# edison_mezzanine_oled.net
KiCad netlist of a schematic drawn in EAGLE
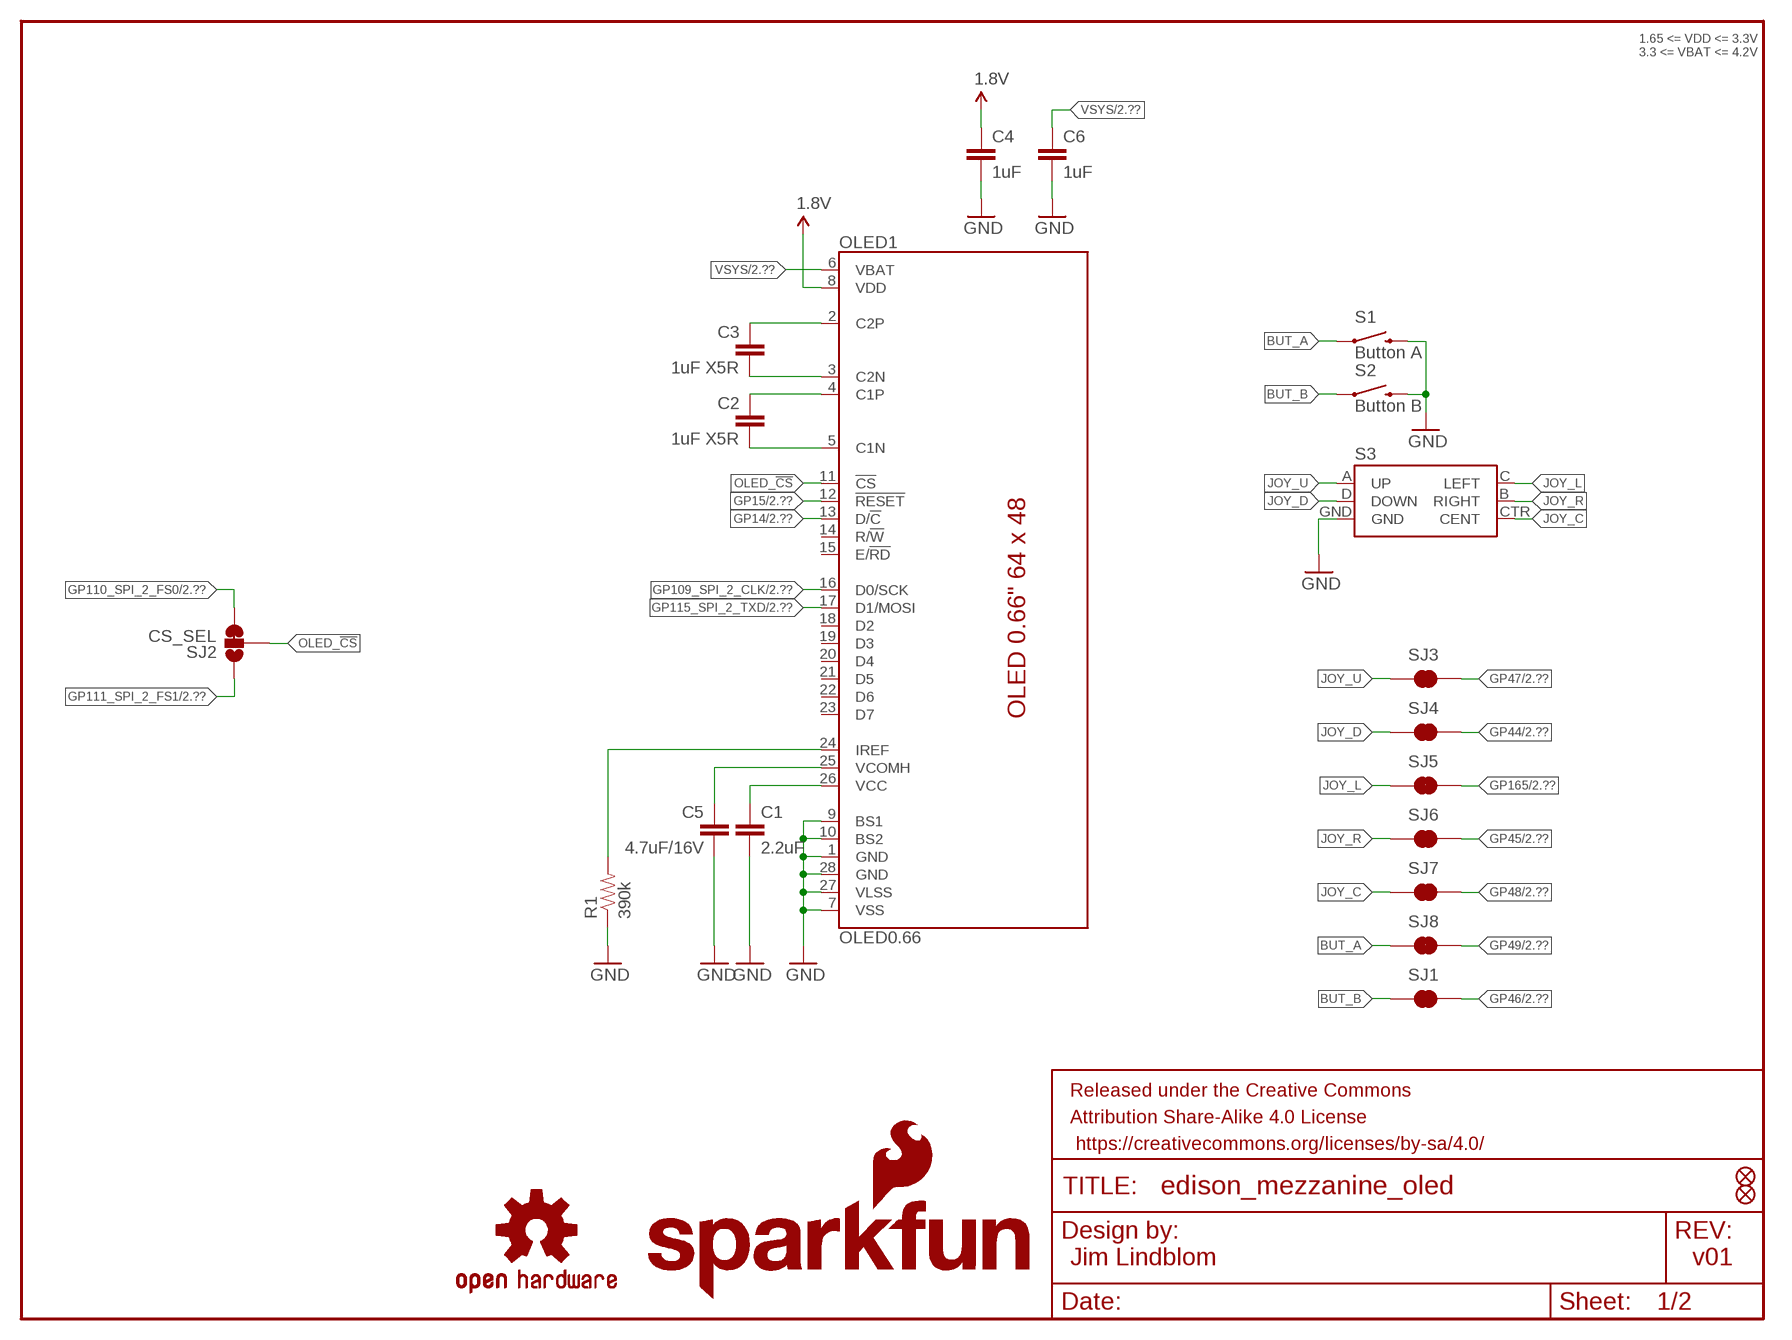
[diagram p0: schematic, sheet 1]
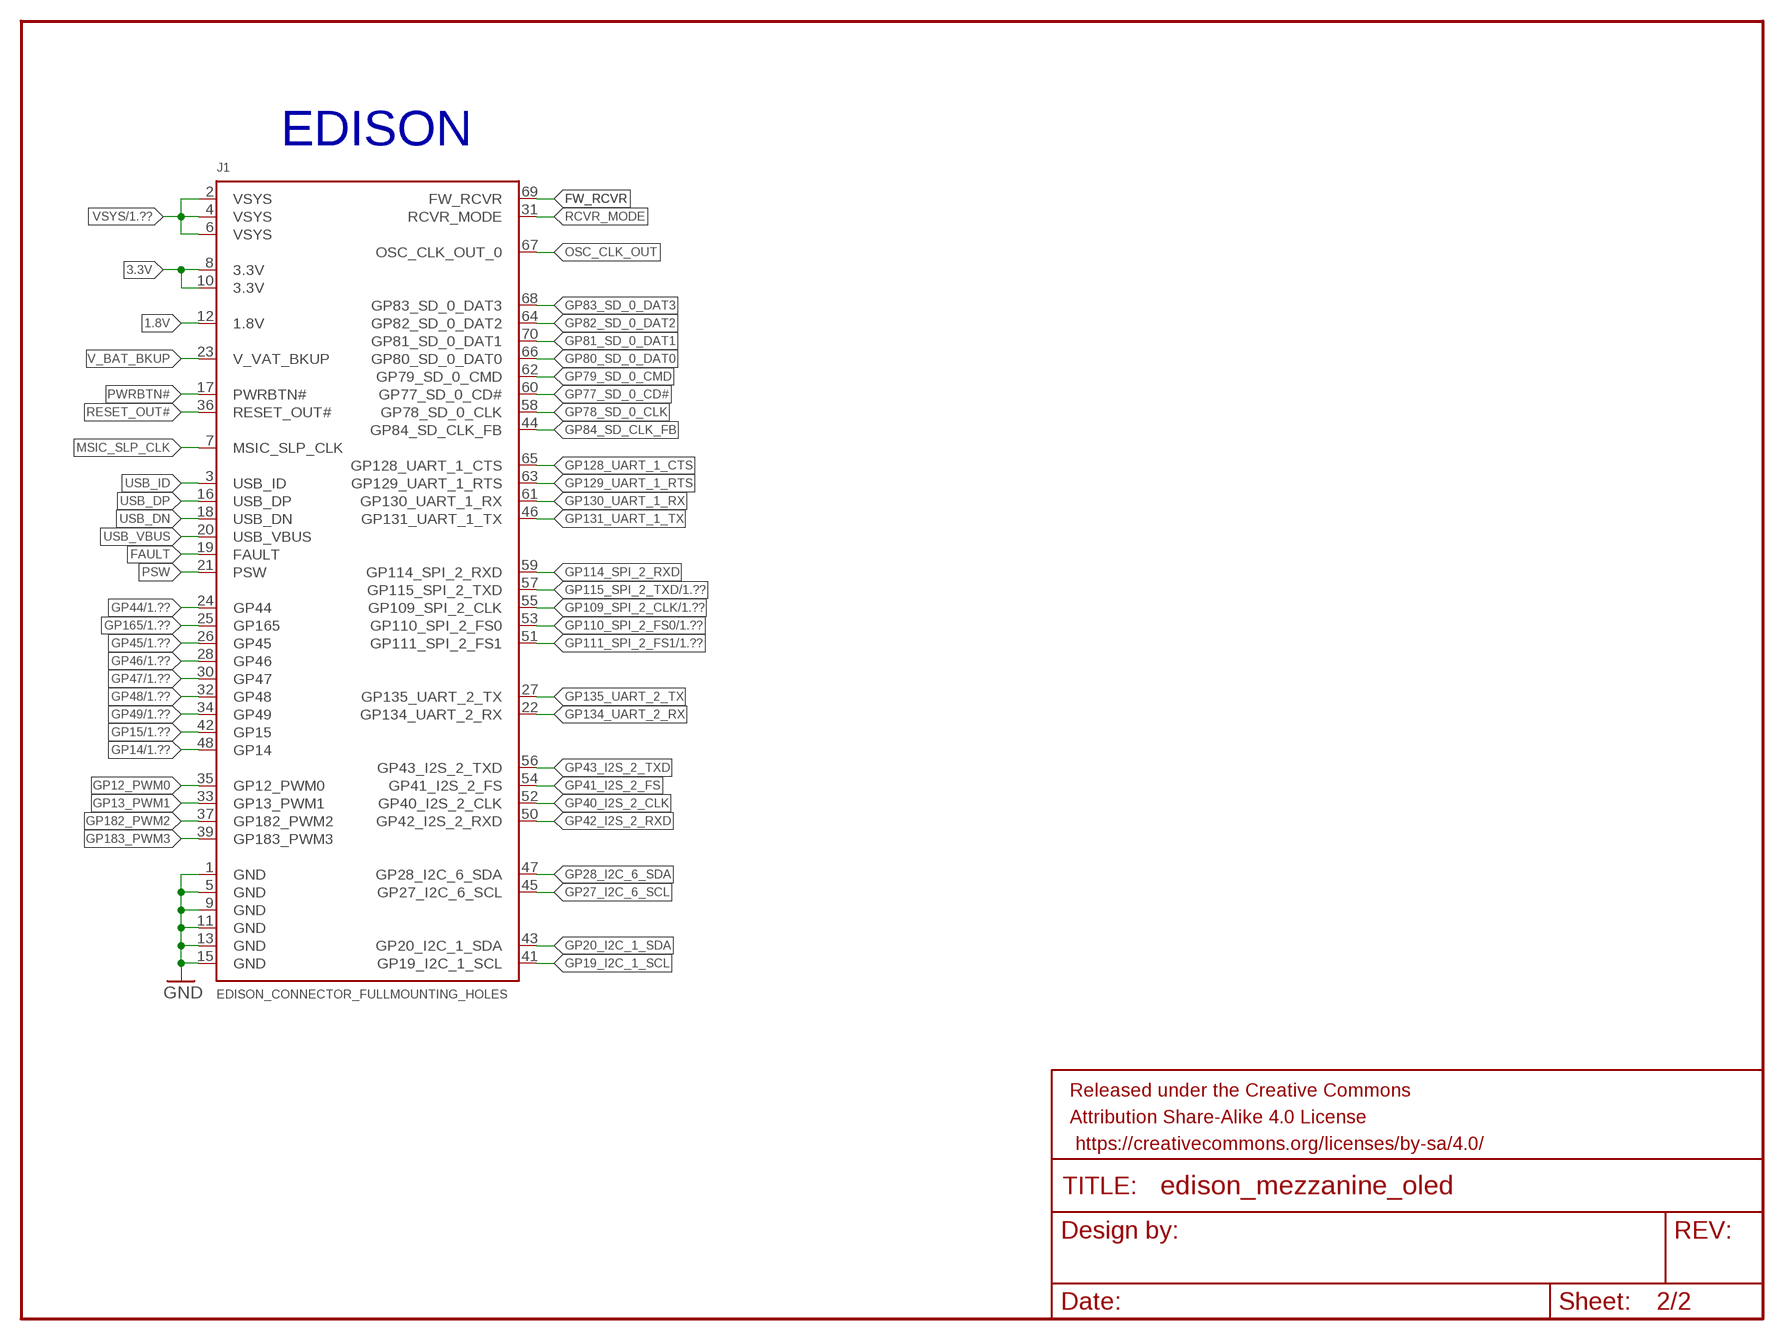
[diagram p1: schematic, sheet 2]

(export (version "E")
  (design (tool "Eeschema 10.0.6"))
  (components
    (comp (ref "C1")
      (value "2.2uF")
      (footprint "eagle-import:0805")
      (libsource (lib "eagle-import") (part "CAP0805"))
    )
    (comp (ref "C2")
      (value "1uF X5R")
      (footprint "eagle-import:0805")
      (libsource (lib "eagle-import") (part "CAP0805"))
    )
    (comp (ref "C3")
      (value "1uF X5R")
      (footprint "eagle-import:0805")
      (libsource (lib "eagle-import") (part "CAP0805"))
    )
    (comp (ref "C4")
      (value "1uF")
      (footprint "eagle-import:0603-CAP")
      (libsource (lib "eagle-import") (part "CAP0603-CAP"))
    )
    (comp (ref "C5")
      (value "4.7uF/16V")
      (footprint "eagle-import:1206")
      (libsource (lib "eagle-import") (part "CAP1206"))
    )
    (comp (ref "C6")
      (value "1uF")
      (footprint "eagle-import:0603-CAP")
      (libsource (lib "eagle-import") (part "CAP0603-CAP"))
    )
    (comp (ref "FID1")
      (value "FIDUCIAL1X2")
      (footprint "eagle-import:FIDUCIAL-1X2")
      (libsource (lib "eagle-import") (part "FIDUCIAL1X2"))
    )
    (comp (ref "FID2")
      (value "FIDUCIAL1X2")
      (footprint "eagle-import:FIDUCIAL-1X2")
      (libsource (lib "eagle-import") (part "FIDUCIAL1X2"))
    )
    (comp (ref "FRAME1")
      (value "FRAME-LETTER")
      (footprint "eagle-import:CREATIVE_COMMONS")
      (libsource (lib "eagle-import") (part "FRAME-LETTER"))
    )
    (comp (ref "LOGO1")
      (value "SFE_LOGO_NAME_FLAME.1_INCH")
      (footprint "eagle-import:SFE_LOGO_NAME_FLAME_.1")
      (libsource (lib "eagle-import") (part "SFE_LOGO_NAME_FLAME.1_INCH"))
    )
    (comp (ref "LOGO2")
      (value "OSHW-LOGOS")
      (footprint "eagle-import:OSHW-LOGO-S")
      (libsource (lib "eagle-import") (part "OSHW-LOGOS"))
    )
    (comp (ref "OLED1")
      (value "OLED0.66")
      (footprint "eagle-import:OLED-0.66-64X48")
      (libsource (lib "eagle-import") (part "OLED0.66"))
    )
    (comp (ref "R1")
      (value "390k")
      (footprint "eagle-import:0603-RES")
      (libsource (lib "eagle-import") (part "RESISTOR0603-RES"))
    )
    (comp (ref "S1")
      (value "Button A")
      (footprint "eagle-import:TACTILE-SWITCH-SMD")
      (libsource (lib "eagle-import") (part "SWITCH-MOMENTARY-2SMD"))
    )
    (comp (ref "S2")
      (value "Button B")
      (footprint "eagle-import:TACTILE-SWITCH-SMD")
      (libsource (lib "eagle-import") (part "SWITCH-MOMENTARY-2SMD"))
    )
    (comp (ref "S3")
      (value "JOYSTICK_MINI")
      (footprint "eagle-import:JOYSTICK_MINI")
      (libsource (lib "eagle-import") (part "JOYSTICK_MINI"))
    )
    (comp (ref "SJ1")
      (value "JUMPER-PAD-2-NC_BY_TRACE")
      (footprint "eagle-import:PAD-JUMPER-2-NC_BY_TRACE_YES_SILK")
      (libsource (lib "eagle-import") (part "JUMPER-PAD-2-NC_BY_TRACE"))
    )
    (comp (ref "SJ2")
      (value "CS_SEL")
      (footprint "eagle-import:PAD-JUMPER-3-2OF3_NC_BY_TRACE_YES_SILK_FULL_BOX")
      (libsource (lib "eagle-import") (part "JUMPER-PAD-3-2OF3_NC_BY_TRACE"))
    )
    (comp (ref "SJ3")
      (value "JUMPER-PAD-2-NC_BY_TRACE")
      (footprint "eagle-import:PAD-JUMPER-2-NC_BY_TRACE_YES_SILK")
      (libsource (lib "eagle-import") (part "JUMPER-PAD-2-NC_BY_TRACE"))
    )
    (comp (ref "SJ4")
      (value "JUMPER-PAD-2-NC_BY_TRACE")
      (footprint "eagle-import:PAD-JUMPER-2-NC_BY_TRACE_YES_SILK")
      (libsource (lib "eagle-import") (part "JUMPER-PAD-2-NC_BY_TRACE"))
    )
    (comp (ref "SJ5")
      (value "JUMPER-PAD-2-NC_BY_TRACE")
      (footprint "eagle-import:PAD-JUMPER-2-NC_BY_TRACE_YES_SILK")
      (libsource (lib "eagle-import") (part "JUMPER-PAD-2-NC_BY_TRACE"))
    )
    (comp (ref "SJ6")
      (value "JUMPER-PAD-2-NC_BY_TRACE")
      (footprint "eagle-import:PAD-JUMPER-2-NC_BY_TRACE_YES_SILK")
      (libsource (lib "eagle-import") (part "JUMPER-PAD-2-NC_BY_TRACE"))
    )
    (comp (ref "SJ7")
      (value "JUMPER-PAD-2-NC_BY_TRACE")
      (footprint "eagle-import:PAD-JUMPER-2-NC_BY_TRACE_YES_SILK")
      (libsource (lib "eagle-import") (part "JUMPER-PAD-2-NC_BY_TRACE"))
    )
    (comp (ref "SJ8")
      (value "JUMPER-PAD-2-NC_BY_TRACE")
      (footprint "eagle-import:PAD-JUMPER-2-NC_BY_TRACE_YES_SILK")
      (libsource (lib "eagle-import") (part "JUMPER-PAD-2-NC_BY_TRACE"))
    )
    (comp (ref "FRAME2")
      (value "FRAME-LETTER")
      (footprint "eagle-import:CREATIVE_COMMONS")
      (libsource (lib "eagle-import") (part "FRAME-LETTER"))
    )
    (comp (ref "J1")
      (value "EDISON_CONNECTOR_FULLMOUNTING_HOLES")
      (footprint "eagle-import:EDISON_DAUGHTER")
      (libsource (lib "eagle-import") (part "EDISON_CONNECTOR_FULLMOUNTING_HOLES"))
    )
  )
  (nets
    (net (code "1") (name "1.8V") (class "Default")
      (node (ref "C4") (pin "1") (pinfunction "1_1") (pintype "passive"))
      (node (ref "J1") (pin "12") (pinfunction "1.8V_12") (pintype "bidirectional"))
      (node (ref "OLED1") (pin "8") (pinfunction "VDD_8") (pintype "bidirectional"))
    )
    (net (code "2") (name "3.3V") (class "Default")
      (node (ref "J1") (pin "10") (pinfunction "3.3V_10") (pintype "bidirectional"))
      (node (ref "J1") (pin "8") (pinfunction "3.3V_8") (pintype "bidirectional"))
    )
    (net (code "3") (name "BUT_A") (class "Default")
      (node (ref "S1") (pin "1") (pinfunction "1_1") (pintype "passive"))
      (node (ref "SJ8") (pin "1") (pinfunction "1_1") (pintype "passive"))
    )
    (net (code "4") (name "BUT_B") (class "Default")
      (node (ref "S2") (pin "1") (pinfunction "1_1") (pintype "passive"))
      (node (ref "SJ1") (pin "1") (pinfunction "1_1") (pintype "passive"))
    )
    (net (code "5") (name "FAULT") (class "Default")
      (node (ref "J1") (pin "19") (pinfunction "FAULT_19") (pintype "bidirectional"))
    )
    (net (code "6") (name "FW_RCVR") (class "Default")
      (node (ref "J1") (pin "69") (pinfunction "FW_RCVR_69") (pintype "bidirectional"))
    )
    (net (code "7") (name "GND") (class "Default")
      (node (ref "C1") (pin "2") (pinfunction "2_2") (pintype "passive"))
      (node (ref "C4") (pin "2") (pinfunction "2_2") (pintype "passive"))
      (node (ref "C5") (pin "2") (pinfunction "2_2") (pintype "passive"))
      (node (ref "C6") (pin "2") (pinfunction "2_2") (pintype "passive"))
      (node (ref "J1") (pin "1") (pinfunction "GND_1") (pintype "bidirectional"))
      (node (ref "J1") (pin "11") (pinfunction "GND_11") (pintype "bidirectional"))
      (node (ref "J1") (pin "13") (pinfunction "GND_13") (pintype "bidirectional"))
      (node (ref "J1") (pin "15") (pinfunction "GND_15") (pintype "bidirectional"))
      (node (ref "J1") (pin "5") (pinfunction "GND_5") (pintype "bidirectional"))
      (node (ref "J1") (pin "9") (pinfunction "GND_9") (pintype "bidirectional"))
      (node (ref "OLED1") (pin "1") (pinfunction "GND_1") (pintype "bidirectional"))
      (node (ref "OLED1") (pin "10") (pinfunction "BS2_10") (pintype "bidirectional"))
      (node (ref "OLED1") (pin "27") (pinfunction "VLSS_27") (pintype "bidirectional"))
      (node (ref "OLED1") (pin "28") (pinfunction "GND_28") (pintype "bidirectional"))
      (node (ref "OLED1") (pin "7") (pinfunction "VSS_7") (pintype "bidirectional"))
      (node (ref "OLED1") (pin "9") (pinfunction "BS1_9") (pintype "bidirectional"))
      (node (ref "R1") (pin "1") (pinfunction "1_1") (pintype "passive"))
      (node (ref "S1") (pin "3") (pinfunction "2_3") (pintype "passive"))
      (node (ref "S2") (pin "3") (pinfunction "2_3") (pintype "passive"))
      (node (ref "S3") (pin "GND") (pinfunction "GND_GND") (pintype "bidirectional"))
    )
    (net (code "8") (name "GP12_PWM0") (class "Default")
      (node (ref "J1") (pin "35") (pinfunction "GP12_PWM0_35") (pintype "bidirectional"))
    )
    (net (code "9") (name "GP13_PWM1") (class "Default")
      (node (ref "J1") (pin "33") (pinfunction "GP13_PWM1_33") (pintype "bidirectional"))
    )
    (net (code "10") (name "GP14") (class "Default")
      (node (ref "J1") (pin "48") (pinfunction "GP14_48") (pintype "bidirectional"))
      (node (ref "OLED1") (pin "13") (pinfunction "D/~{C}_13") (pintype "bidirectional"))
    )
    (net (code "11") (name "GP15") (class "Default")
      (node (ref "J1") (pin "42") (pinfunction "GP15_42") (pintype "bidirectional"))
      (node (ref "OLED1") (pin "12") (pinfunction "~{RESET}_12") (pintype "bidirectional"))
    )
    (net (code "12") (name "GP19_I2C_1_SCL") (class "Default")
      (node (ref "J1") (pin "41") (pinfunction "GP19_I2C_1_SCL_41") (pintype "bidirectional"))
    )
    (net (code "13") (name "GP20_I2C_1_SDA") (class "Default")
      (node (ref "J1") (pin "43") (pinfunction "GP20_I2C_1_SDA_43") (pintype "bidirectional"))
    )
    (net (code "14") (name "GP27_I2C_6_SCL") (class "Default")
      (node (ref "J1") (pin "45") (pinfunction "GP27_I2C_6_SCL_45") (pintype "bidirectional"))
    )
    (net (code "15") (name "GP28_I2C_6_SDA") (class "Default")
      (node (ref "J1") (pin "47") (pinfunction "GP28_I2C_6_SDA_47") (pintype "bidirectional"))
    )
    (net (code "16") (name "GP40_I2S_2_CLK") (class "Default")
      (node (ref "J1") (pin "52") (pinfunction "GP40_I2S_2_CLK_52") (pintype "bidirectional"))
    )
    (net (code "17") (name "GP41_I2S_2_FS") (class "Default")
      (node (ref "J1") (pin "54") (pinfunction "GP41_I2S_2_FS_54") (pintype "bidirectional"))
    )
    (net (code "18") (name "GP42_I2S_2_RXD") (class "Default")
      (node (ref "J1") (pin "50") (pinfunction "GP42_I2S_2_RXD_50") (pintype "bidirectional"))
    )
    (net (code "19") (name "GP43_I2S_2_TXD") (class "Default")
      (node (ref "J1") (pin "56") (pinfunction "GP43_I2S_2_TXD_56") (pintype "bidirectional"))
    )
    (net (code "20") (name "GP44") (class "Default")
      (node (ref "J1") (pin "24") (pinfunction "GP44_24") (pintype "bidirectional"))
      (node (ref "SJ4") (pin "2") (pinfunction "2_2") (pintype "passive"))
    )
    (net (code "21") (name "GP45") (class "Default")
      (node (ref "J1") (pin "26") (pinfunction "GP45_26") (pintype "bidirectional"))
      (node (ref "SJ6") (pin "2") (pinfunction "2_2") (pintype "passive"))
    )
    (net (code "22") (name "GP46") (class "Default")
      (node (ref "J1") (pin "28") (pinfunction "GP46_28") (pintype "bidirectional"))
      (node (ref "SJ1") (pin "2") (pinfunction "2_2") (pintype "passive"))
    )
    (net (code "23") (name "GP47") (class "Default")
      (node (ref "J1") (pin "30") (pinfunction "GP47_30") (pintype "bidirectional"))
      (node (ref "SJ3") (pin "2") (pinfunction "2_2") (pintype "passive"))
    )
    (net (code "24") (name "GP48") (class "Default")
      (node (ref "J1") (pin "32") (pinfunction "GP48_32") (pintype "bidirectional"))
      (node (ref "SJ7") (pin "2") (pinfunction "2_2") (pintype "passive"))
    )
    (net (code "25") (name "GP49") (class "Default")
      (node (ref "J1") (pin "34") (pinfunction "GP49_34") (pintype "bidirectional"))
      (node (ref "SJ8") (pin "2") (pinfunction "2_2") (pintype "passive"))
    )
    (net (code "26") (name "GP77_SD_0_CD#") (class "Default")
      (node (ref "J1") (pin "60") (pinfunction "GP77_SD_0_CD#_60") (pintype "bidirectional"))
    )
    (net (code "27") (name "GP78_SD_0_CLK") (class "Default")
      (node (ref "J1") (pin "58") (pinfunction "GP78_SD_0_CLK_58") (pintype "bidirectional"))
    )
    (net (code "28") (name "GP79_SD_0_CMD") (class "Default")
      (node (ref "J1") (pin "62") (pinfunction "GP79_SD_0_CMD_62") (pintype "bidirectional"))
    )
    (net (code "29") (name "GP80_SD_0_DAT0") (class "Default")
      (node (ref "J1") (pin "66") (pinfunction "GP80_SD_0_DAT0_66") (pintype "bidirectional"))
    )
    (net (code "30") (name "GP81_SD_0_DAT1") (class "Default")
      (node (ref "J1") (pin "70") (pinfunction "GP81_SD_0_DAT1_70") (pintype "bidirectional"))
    )
    (net (code "31") (name "GP82_SD_0_DAT2") (class "Default")
      (node (ref "J1") (pin "64") (pinfunction "GP82_SD_0_DAT2_64") (pintype "bidirectional"))
    )
    (net (code "32") (name "GP83_SD_0_DAT3") (class "Default")
      (node (ref "J1") (pin "68") (pinfunction "GP83_SD_0_DAT3_68") (pintype "bidirectional"))
    )
    (net (code "33") (name "GP84_SD_CLK_FB") (class "Default")
      (node (ref "J1") (pin "44") (pinfunction "GP84_SD_CLK_FB_44") (pintype "bidirectional"))
    )
    (net (code "34") (name "GP109_SPI_2_CLK") (class "Default")
      (node (ref "J1") (pin "55") (pinfunction "GP109_SPI_2_CLK_55") (pintype "bidirectional"))
      (node (ref "OLED1") (pin "16") (pinfunction "D0/SCK_16") (pintype "bidirectional"))
    )
    (net (code "35") (name "GP110_SPI_2_FS0") (class "Default")
      (node (ref "J1") (pin "53") (pinfunction "GP110_SPI_2_FS0_53") (pintype "bidirectional"))
      (node (ref "SJ2") (pin "3") (pinfunction "3_3") (pintype "passive"))
    )
    (net (code "36") (name "GP111_SPI_2_FS1") (class "Default")
      (node (ref "J1") (pin "51") (pinfunction "GP111_SPI_2_FS1_51") (pintype "bidirectional"))
      (node (ref "SJ2") (pin "1") (pinfunction "1_1") (pintype "passive"))
    )
    (net (code "37") (name "GP114_SPI_2_RXD") (class "Default")
      (node (ref "J1") (pin "59") (pinfunction "GP114_SPI_2_RXD_59") (pintype "bidirectional"))
    )
    (net (code "38") (name "GP115_SPI_2_TXD") (class "Default")
      (node (ref "J1") (pin "57") (pinfunction "GP115_SPI_2_TXD_57") (pintype "bidirectional"))
      (node (ref "OLED1") (pin "17") (pinfunction "D1/MOSI_17") (pintype "bidirectional"))
    )
    (net (code "39") (name "GP128_UART_1_CTS") (class "Default")
      (node (ref "J1") (pin "65") (pinfunction "GP128_UART_1_CTS_65") (pintype "bidirectional"))
    )
    (net (code "40") (name "GP129_UART_1_RTS") (class "Default")
      (node (ref "J1") (pin "63") (pinfunction "GP129_UART_1_RTS_63") (pintype "bidirectional"))
    )
    (net (code "41") (name "GP130_UART_1_RX") (class "Default")
      (node (ref "J1") (pin "61") (pinfunction "GP130_UART_1_RX_61") (pintype "bidirectional"))
    )
    (net (code "42") (name "GP131_UART_1_TX") (class "Default")
      (node (ref "J1") (pin "46") (pinfunction "GP131_UART_1_TX_46") (pintype "bidirectional"))
    )
    (net (code "43") (name "GP134_UART_2_RX") (class "Default")
      (node (ref "J1") (pin "22") (pinfunction "GP134_UART_2_RX_22") (pintype "bidirectional"))
    )
    (net (code "44") (name "GP135_UART_2_TX") (class "Default")
      (node (ref "J1") (pin "27") (pinfunction "GP135_UART_2_TX_27") (pintype "bidirectional"))
    )
    (net (code "45") (name "GP165") (class "Default")
      (node (ref "J1") (pin "25") (pinfunction "GP165_25") (pintype "bidirectional"))
      (node (ref "SJ5") (pin "2") (pinfunction "2_2") (pintype "passive"))
    )
    (net (code "46") (name "GP182_PWM2") (class "Default")
      (node (ref "J1") (pin "37") (pinfunction "GP182_PWM2_37") (pintype "bidirectional"))
    )
    (net (code "47") (name "GP183_PWM3") (class "Default")
      (node (ref "J1") (pin "39") (pinfunction "GP183_PWM3_39") (pintype "bidirectional"))
    )
    (net (code "48") (name "JOY_C") (class "Default")
      (node (ref "S3") (pin "CTR") (pinfunction "CENT_CTR") (pintype "bidirectional"))
      (node (ref "SJ7") (pin "1") (pinfunction "1_1") (pintype "passive"))
    )
    (net (code "49") (name "JOY_D") (class "Default")
      (node (ref "S3") (pin "D") (pinfunction "DOWN_D") (pintype "bidirectional"))
      (node (ref "SJ4") (pin "1") (pinfunction "1_1") (pintype "passive"))
    )
    (net (code "50") (name "JOY_L") (class "Default")
      (node (ref "S3") (pin "C") (pinfunction "LEFT_C") (pintype "bidirectional"))
      (node (ref "SJ5") (pin "1") (pinfunction "1_1") (pintype "passive"))
    )
    (net (code "51") (name "JOY_R") (class "Default")
      (node (ref "S3") (pin "B") (pinfunction "RIGHT_B") (pintype "bidirectional"))
      (node (ref "SJ6") (pin "1") (pinfunction "1_1") (pintype "passive"))
    )
    (net (code "52") (name "JOY_U") (class "Default")
      (node (ref "S3") (pin "A") (pinfunction "UP_A") (pintype "bidirectional"))
      (node (ref "SJ3") (pin "1") (pinfunction "1_1") (pintype "passive"))
    )
    (net (code "53") (name "MSIC_SLP_CLK") (class "Default")
      (node (ref "J1") (pin "7") (pinfunction "MSIC_SLP_CLK_7") (pintype "bidirectional"))
    )
    (net (code "54") (name "Net-(OLED1-C1N)") (class "Default")
      (node (ref "C2") (pin "2") (pinfunction "2_2") (pintype "passive"))
      (node (ref "OLED1") (pin "5") (pinfunction "C1N_5") (pintype "bidirectional"))
    )
    (net (code "55") (name "Net-(OLED1-C1P)") (class "Default")
      (node (ref "C2") (pin "1") (pinfunction "1_1") (pintype "passive"))
      (node (ref "OLED1") (pin "4") (pinfunction "C1P_4") (pintype "bidirectional"))
    )
    (net (code "56") (name "Net-(OLED1-C2N)") (class "Default")
      (node (ref "C3") (pin "2") (pinfunction "2_2") (pintype "passive"))
      (node (ref "OLED1") (pin "3") (pinfunction "C2N_3") (pintype "bidirectional"))
    )
    (net (code "57") (name "Net-(OLED1-C2P)") (class "Default")
      (node (ref "C3") (pin "1") (pinfunction "1_1") (pintype "passive"))
      (node (ref "OLED1") (pin "2") (pinfunction "C2P_2") (pintype "bidirectional"))
    )
    (net (code "58") (name "Net-(OLED1-IREF)") (class "Default")
      (node (ref "OLED1") (pin "24") (pinfunction "IREF_24") (pintype "bidirectional"))
      (node (ref "R1") (pin "2") (pinfunction "2_2") (pintype "passive"))
    )
    (net (code "59") (name "Net-(OLED1-VCC)") (class "Default")
      (node (ref "C1") (pin "1") (pinfunction "1_1") (pintype "passive"))
      (node (ref "OLED1") (pin "26") (pinfunction "VCC_26") (pintype "bidirectional"))
    )
    (net (code "60") (name "Net-(OLED1-VCOMH)") (class "Default")
      (node (ref "C5") (pin "1") (pinfunction "1_1") (pintype "passive"))
      (node (ref "OLED1") (pin "25") (pinfunction "VCOMH_25") (pintype "bidirectional"))
    )
    (net (code "61") (name "OLED_~{CS}") (class "Default")
      (node (ref "OLED1") (pin "11") (pinfunction "~{CS}_11") (pintype "bidirectional"))
      (node (ref "SJ2") (pin "2") (pinfunction "2_2") (pintype "passive"))
    )
    (net (code "62") (name "OSC_CLK_OUT") (class "Default")
      (node (ref "J1") (pin "67") (pinfunction "OSC_CLK_OUT_0_67") (pintype "bidirectional"))
    )
    (net (code "63") (name "PSW") (class "Default")
      (node (ref "J1") (pin "21") (pinfunction "PSW_21") (pintype "bidirectional"))
    )
    (net (code "64") (name "PWRBTN#") (class "Default")
      (node (ref "J1") (pin "17") (pinfunction "PWRBTN#_17") (pintype "bidirectional"))
    )
    (net (code "65") (name "RCVR_MODE") (class "Default")
      (node (ref "J1") (pin "31") (pinfunction "RCVR_MODE_31") (pintype "bidirectional"))
    )
    (net (code "66") (name "RESET_OUT#") (class "Default")
      (node (ref "J1") (pin "36") (pinfunction "RESET_OUT#_36") (pintype "bidirectional"))
    )
    (net (code "67") (name "USB_DN") (class "Default")
      (node (ref "J1") (pin "18") (pinfunction "USB_DN_18") (pintype "bidirectional"))
    )
    (net (code "68") (name "USB_DP") (class "Default")
      (node (ref "J1") (pin "16") (pinfunction "USB_DP_16") (pintype "bidirectional"))
    )
    (net (code "69") (name "USB_ID") (class "Default")
      (node (ref "J1") (pin "3") (pinfunction "USB_ID_3") (pintype "bidirectional"))
    )
    (net (code "70") (name "USB_VBUS") (class "Default")
      (node (ref "J1") (pin "20") (pinfunction "USB_VBUS_20") (pintype "bidirectional"))
    )
    (net (code "71") (name "VSYS") (class "Default")
      (node (ref "C6") (pin "1") (pinfunction "1_1") (pintype "passive"))
      (node (ref "J1") (pin "2") (pinfunction "VSYS_2") (pintype "bidirectional"))
      (node (ref "J1") (pin "4") (pinfunction "VSYS_4") (pintype "bidirectional"))
      (node (ref "J1") (pin "6") (pinfunction "VSYS_6") (pintype "bidirectional"))
      (node (ref "OLED1") (pin "6") (pinfunction "VBAT_6") (pintype "bidirectional"))
    )
    (net (code "72") (name "V_BAT_BKUP") (class "Default")
      (node (ref "J1") (pin "23") (pinfunction "V_VAT_BKUP_23") (pintype "bidirectional"))
    )
    (net (code "73") (name "unconnected-(OLED1-D2-Pad18)") (class "Default")
      (node (ref "OLED1") (pin "18") (pinfunction "D2_18") (pintype "bidirectional"))
    )
    (net (code "74") (name "unconnected-(OLED1-D3-Pad19)") (class "Default")
      (node (ref "OLED1") (pin "19") (pinfunction "D3_19") (pintype "bidirectional"))
    )
    (net (code "75") (name "unconnected-(OLED1-D4-Pad20)") (class "Default")
      (node (ref "OLED1") (pin "20") (pinfunction "D4_20") (pintype "bidirectional"))
    )
    (net (code "76") (name "unconnected-(OLED1-D5-Pad21)") (class "Default")
      (node (ref "OLED1") (pin "21") (pinfunction "D5_21") (pintype "bidirectional"))
    )
    (net (code "77") (name "unconnected-(OLED1-D6-Pad22)") (class "Default")
      (node (ref "OLED1") (pin "22") (pinfunction "D6_22") (pintype "bidirectional"))
    )
    (net (code "78") (name "unconnected-(OLED1-D7-Pad23)") (class "Default")
      (node (ref "OLED1") (pin "23") (pinfunction "D7_23") (pintype "bidirectional"))
    )
    (net (code "79") (name "unconnected-(OLED1-E{slash}~{RD}-Pad15)") (class "Default")
      (node (ref "OLED1") (pin "15") (pinfunction "E/~{RD}_15") (pintype "bidirectional"))
    )
    (net (code "80") (name "unconnected-(OLED1-R{slash}~{W}-Pad14)") (class "Default")
      (node (ref "OLED1") (pin "14") (pinfunction "R/~{W}_14") (pintype "bidirectional"))
    )
  )
)
